# FM-Super-Regen-Alt.net
KiCad netlist of a schematic drawn in EAGLE
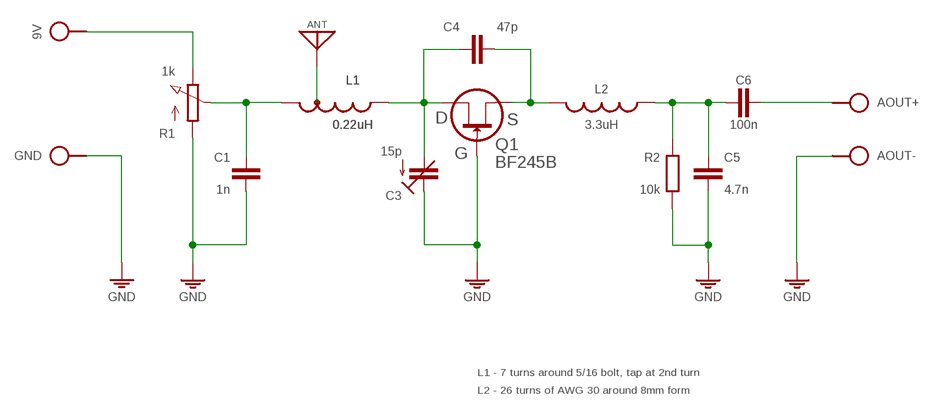
[diagram p0: schematic, sheet 1]

(export (version "E")
  (design (tool "Eeschema 10.0.6"))
  (components
    (comp (ref "9V")
      (value "SPAD")
      (footprint "eagle-import:SPAD")
      (libsource (lib "eagle-import") (part "SPAD"))
    )
    (comp (ref "ANT")
      (value "ANT")
      (footprint "eagle-import:SPAD")
      (libsource (lib "eagle-import") (part "ANT"))
    )
    (comp (ref "AOUT+")
      (value "SPAD")
      (footprint "eagle-import:SPAD")
      (libsource (lib "eagle-import") (part "SPAD"))
    )
    (comp (ref "AOUT-")
      (value "SPAD")
      (footprint "eagle-import:SPAD")
      (libsource (lib "eagle-import") (part "SPAD"))
    )
    (comp (ref "C1")
      (value "1n")
      (footprint "eagle-import:C050-020X036_V")
      (libsource (lib "eagle-import") (part "C050-020X036/V"))
    )
    (comp (ref "C3")
      (value "15p")
      (footprint "eagle-import:TRIM-2222-808")
      (libsource (lib "eagle-import") (part "C-TR-PH201272222-808-2PIN"))
    )
    (comp (ref "C4")
      (value "47p")
      (footprint "eagle-import:C050-020X036")
      (libsource (lib "eagle-import") (part "C050-020X036"))
    )
    (comp (ref "C5")
      (value "4.7n")
      (footprint "eagle-import:C050-020X036")
      (libsource (lib "eagle-import") (part "C050-020X036"))
    )
    (comp (ref "C6")
      (value "100n")
      (footprint "eagle-import:C050-020X036")
      (libsource (lib "eagle-import") (part "C050-020X036"))
    )
    (comp (ref "GND")
      (value "SPAD")
      (footprint "eagle-import:SPAD")
      (libsource (lib "eagle-import") (part "SPAD"))
    )
    (comp (ref "L1")
      (value "0.22uH")
      (footprint "eagle-import:L-08_7V-TAP1")
      (libsource (lib "eagle-import") (part "L-TAP108/7V"))
    )
    (comp (ref "L2")
      (value "3.3uH")
      (footprint "eagle-import:L-BODY")
      (libsource (lib "eagle-import") (part "L-BODY"))
    )
    (comp (ref "Q1")
      (value "BF245B")
      (footprint "eagle-import:TO92")
      (libsource (lib "eagle-import") (part "BF245B"))
    )
    (comp (ref "R1")
      (value "1k")
      (footprint "eagle-import:POT-V")
      (libsource (lib "eagle-import") (part "POT-V"))
    )
    (comp (ref "R2")
      (value "10k")
      (footprint "eagle-import:0204_10")
      (libsource (lib "eagle-import") (part "R0204/10"))
    )
  )
  (nets
    (net (code "1") (name "GND") (class "Default")
      (node (ref "AOUT-") (pin "1") (pinfunction "P$1_1") (pintype "bidirectional"))
      (node (ref "C1") (pin "2") (pinfunction "2_2") (pintype "passive"))
      (node (ref "C3") (pin "1") (pinfunction "E_1") (pintype "passive"))
      (node (ref "C5") (pin "2") (pinfunction "2_2") (pintype "passive"))
      (node (ref "GND") (pin "1") (pinfunction "P$1_1") (pintype "bidirectional"))
      (node (ref "Q1") (pin "1") (pinfunction "G_1") (pintype "passive"))
      (node (ref "R1") (pin "A") (pinfunction "A_A") (pintype "passive"))
      (node (ref "R2") (pin "1") (pinfunction "1_1") (pintype "passive"))
    )
    (net (code "2") (name "Net-(9V-P$1)") (class "Default")
      (node (ref "9V") (pin "1") (pinfunction "P$1_1") (pintype "bidirectional"))
      (node (ref "R1") (pin "E") (pinfunction "E_E") (pintype "passive"))
    )
    (net (code "3") (name "Net-(ANT-Pad1)") (class "Default")
      (node (ref "ANT") (pin "1") (pinfunction "1_1") (pintype "output"))
      (node (ref "L1") (pin "T") (pinfunction "T_T") (pintype "passive"))
    )
    (net (code "4") (name "Net-(AOUT+-P$1)") (class "Default")
      (node (ref "AOUT+") (pin "1") (pinfunction "P$1_1") (pintype "bidirectional"))
      (node (ref "C6") (pin "2") (pinfunction "2_2") (pintype "passive"))
    )
    (net (code "5") (name "Net-(C1-Pad1)") (class "Default")
      (node (ref "C1") (pin "1") (pinfunction "1_1") (pintype "passive"))
      (node (ref "L1") (pin "1") (pinfunction "1_1") (pintype "passive"))
      (node (ref "R1") (pin "S") (pinfunction "S_S") (pintype "passive"))
    )
    (net (code "6") (name "Net-(C3-A)") (class "Default")
      (node (ref "C3") (pin "2") (pinfunction "A_2") (pintype "passive"))
      (node (ref "C4") (pin "1") (pinfunction "1_1") (pintype "passive"))
      (node (ref "L1") (pin "2") (pinfunction "2_2") (pintype "passive"))
      (node (ref "Q1") (pin "3") (pinfunction "D_3") (pintype "passive"))
    )
    (net (code "7") (name "Net-(L2-1)") (class "Default")
      (node (ref "C5") (pin "1") (pinfunction "1_1") (pintype "passive"))
      (node (ref "C6") (pin "1") (pinfunction "1_1") (pintype "passive"))
      (node (ref "L2") (pin "2") (pinfunction "1_2") (pintype "passive"))
      (node (ref "R2") (pin "2") (pinfunction "2_2") (pintype "passive"))
    )
    (net (code "8") (name "Net-(L2-2)") (class "Default")
      (node (ref "C4") (pin "2") (pinfunction "2_2") (pintype "passive"))
      (node (ref "L2") (pin "3") (pinfunction "2_3") (pintype "passive"))
      (node (ref "Q1") (pin "2") (pinfunction "S_2") (pintype "passive"))
    )
  )
)
